# AFPGA_power.net
KiCad netlist of a schematic drawn in Altium Designer
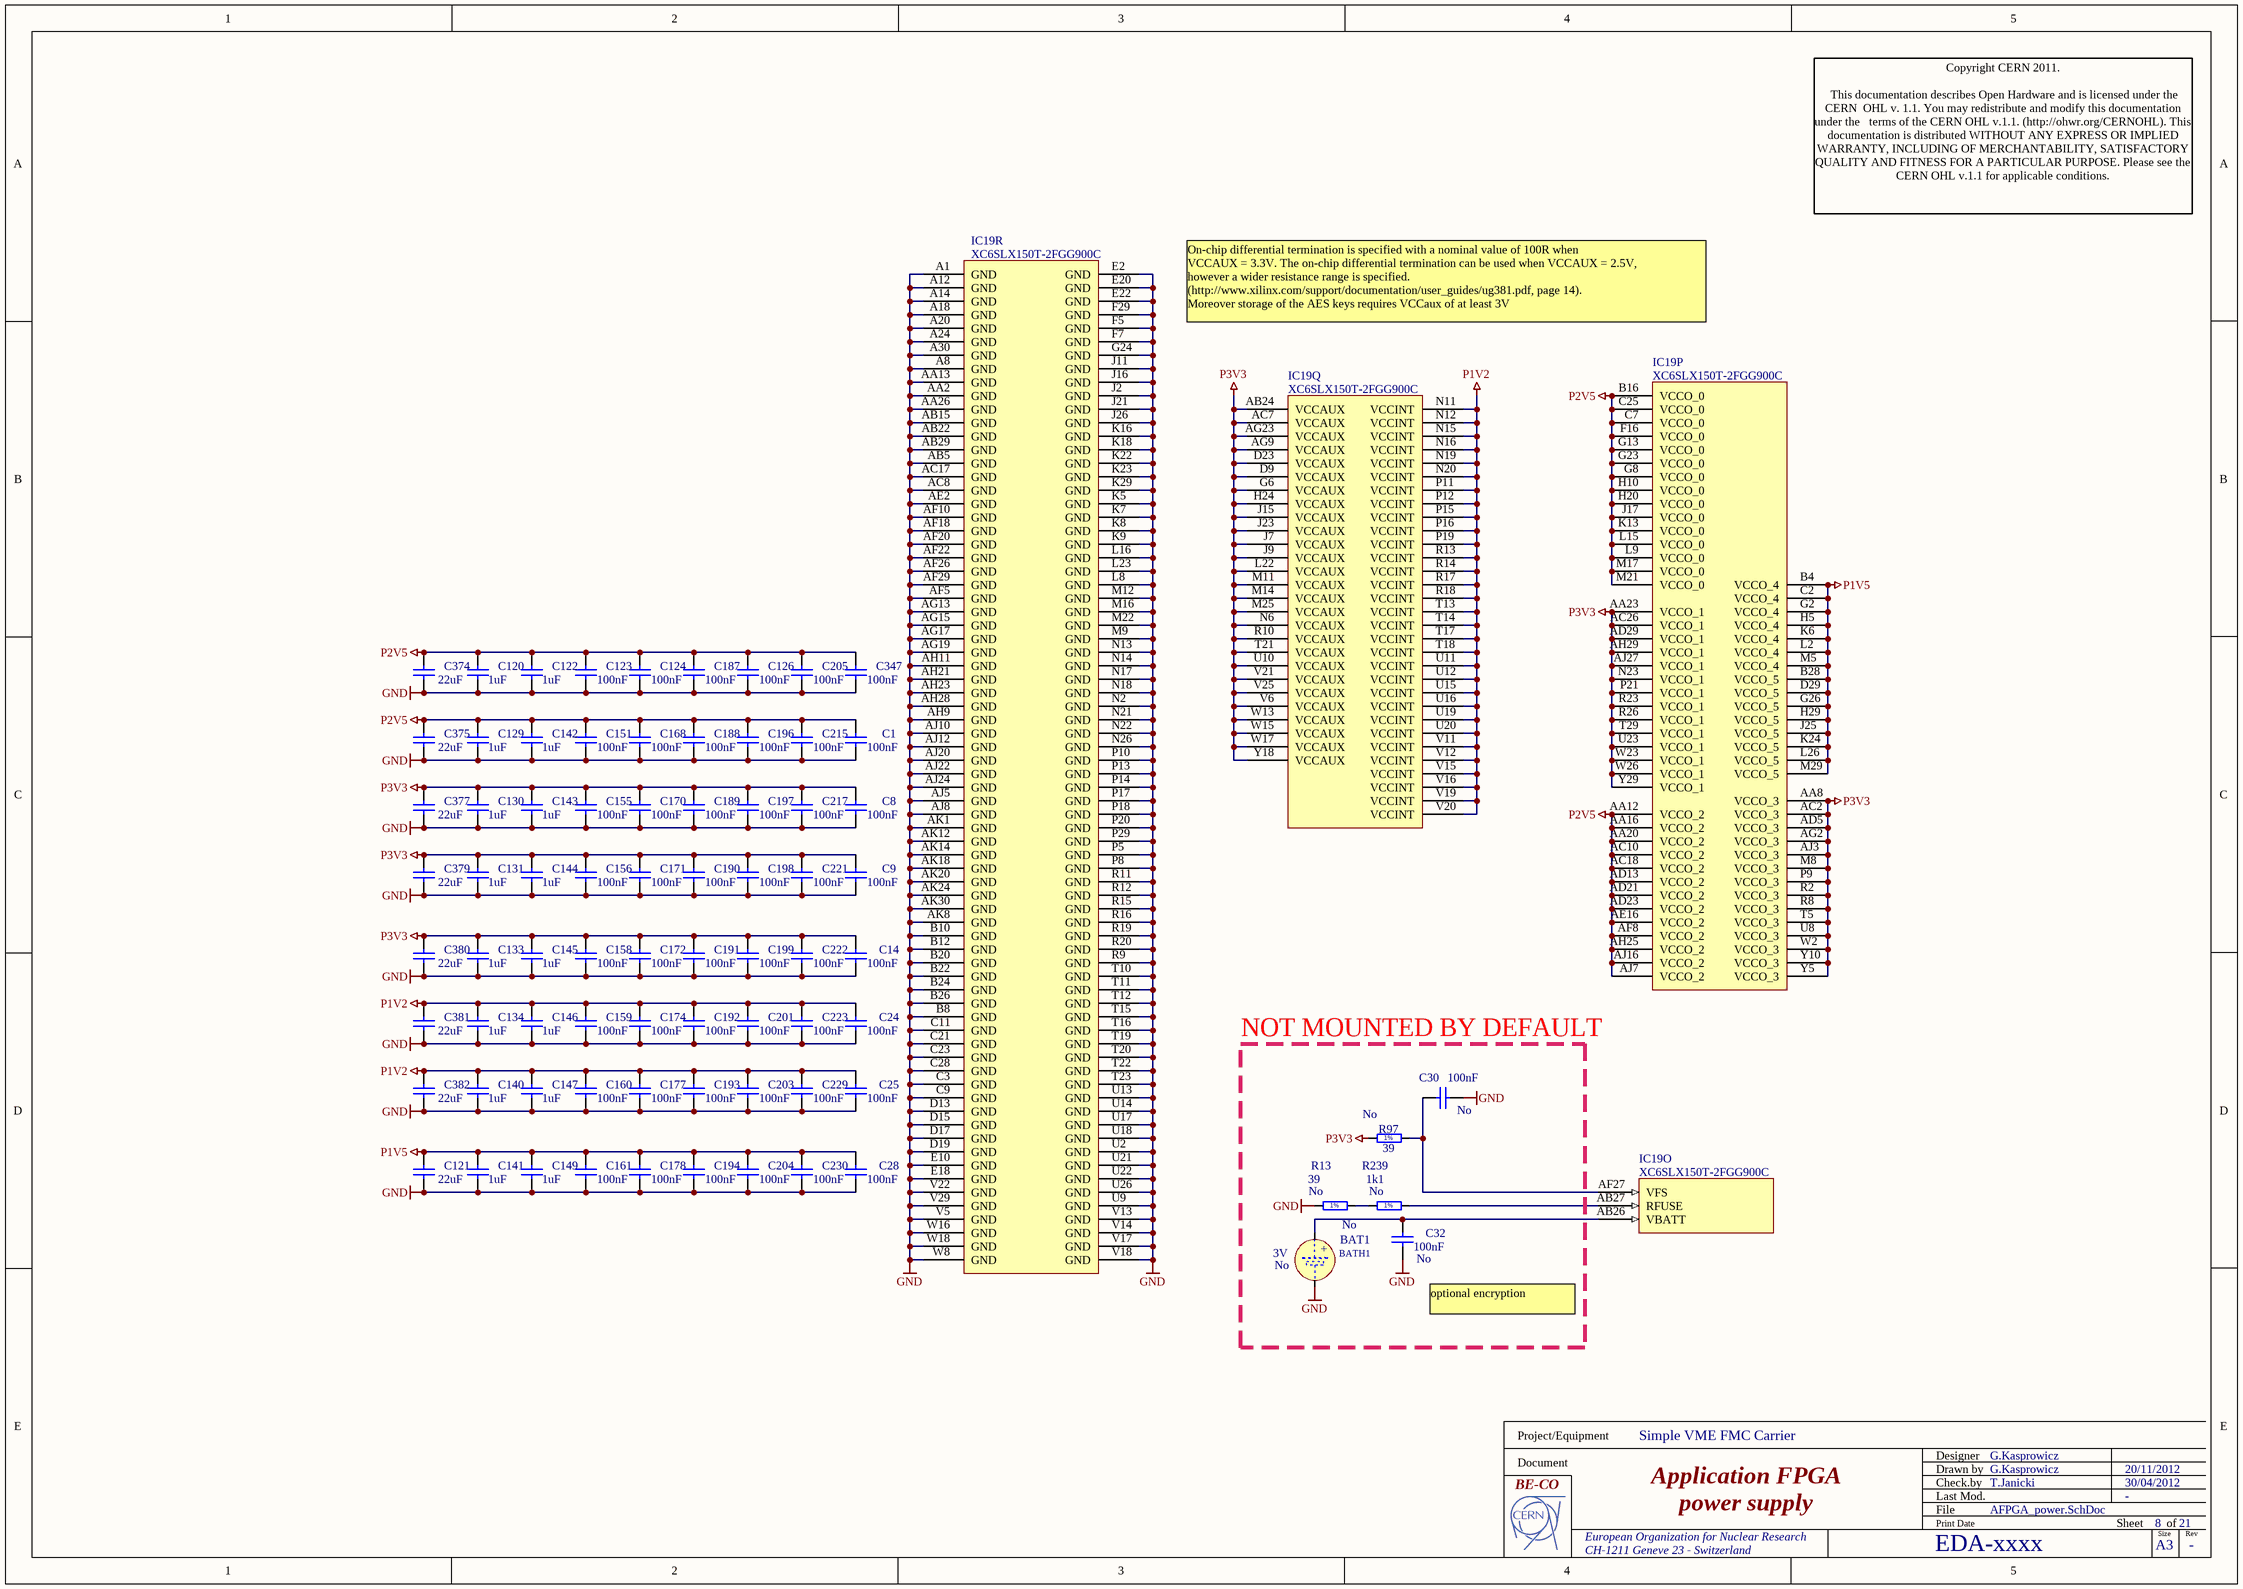
[diagram p0: AFPGA_power.SchDoc]

(export (version "E")
  (design (tool "Eeschema 10.0.6"))
  (components
    (comp (ref "BAT1")
      (value "3V")
      (footprint "BAT_VARTA_CR1220")
      (description "Battery for use only with Socket Holder")
      (fields
        (field (name "PART NUMBER") "BAT_VARTA_CR1220")
        (field (name "MOUNTED") "No")
        (field (name "POWER") "35mAh")
        (field (name "AUTHOR") "CERN DEM JLC")
      )
      (libsource (lib "Eletro-mechanical") (part "Battery No Pin"))
    )
    (comp (ref "BATH1")
      (value "~")
      (footprint "BATH_KEYSTONE_3000")
      (description "Battery Holder whit 2 Pin")
      (fields
        (field (name "PART NUMBER") "BATH_KEYSTONE_3000")
        (field (name "MOUNTED") "No")
        (field (name "MANUFACTURER") "KEYSTONE")
        (field (name "AUTHOR") "CERN DEM JLC")
      )
      (libsource (lib "Eletro-mechanical") (part "Battery Holder 2 Pin"))
    )
    (comp (ref "C1")
      (value "100nF")
      (footprint "CAPC1005X55N")
      (description "Non-polarised capacitor")
      (fields
        (field (name "PART NUMBER") "CC0402_100NF_16V_10%_X7R")
        (field (name "VOLTAGE") "16V")
        (field (name "AUTHOR") "CERN DEM JLC")
      )
      (libsource (lib "Capacitors") (part "Capacitor - non polarized"))
    )
    (comp (ref "C8")
      (value "100nF")
      (footprint "CAPC1005X55N")
      (description "Non-polarised capacitor")
      (fields
        (field (name "PART NUMBER") "CC0402_100NF_16V_10%_X7R")
        (field (name "VOLTAGE") "16V")
        (field (name "AUTHOR") "CERN DEM JLC")
      )
      (libsource (lib "Capacitors") (part "Capacitor - non polarized"))
    )
    (comp (ref "C9")
      (value "100nF")
      (footprint "CAPC1005X55N")
      (description "Non-polarised capacitor")
      (fields
        (field (name "PART NUMBER") "CC0402_100NF_16V_10%_X7R")
        (field (name "VOLTAGE") "16V")
        (field (name "AUTHOR") "CERN DEM JLC")
      )
      (libsource (lib "Capacitors") (part "Capacitor - non polarized"))
    )
    (comp (ref "C14")
      (value "100nF")
      (footprint "CAPC1005X55N")
      (description "Non-polarised capacitor")
      (fields
        (field (name "PART NUMBER") "CC0402_100NF_16V_10%_X7R")
        (field (name "VOLTAGE") "16V")
        (field (name "AUTHOR") "CERN DEM JLC")
      )
      (libsource (lib "Capacitors") (part "Capacitor - non polarized"))
    )
    (comp (ref "C24")
      (value "100nF")
      (footprint "CAPC1005X55N")
      (description "Non-polarised capacitor")
      (fields
        (field (name "PART NUMBER") "CC0402_100NF_16V_10%_X7R")
        (field (name "VOLTAGE") "16V")
        (field (name "AUTHOR") "CERN DEM JLC")
      )
      (libsource (lib "Capacitors") (part "Capacitor - non polarized"))
    )
    (comp (ref "C25")
      (value "100nF")
      (footprint "CAPC1005X55N")
      (description "Non-polarised capacitor")
      (fields
        (field (name "PART NUMBER") "CC0402_100NF_16V_10%_X7R")
        (field (name "VOLTAGE") "16V")
        (field (name "AUTHOR") "CERN DEM JLC")
      )
      (libsource (lib "Capacitors") (part "Capacitor - non polarized"))
    )
    (comp (ref "C28")
      (value "100nF")
      (footprint "CAPC1005X55N")
      (description "Non-polarised capacitor")
      (fields
        (field (name "PART NUMBER") "CC0402_100NF_16V_10%_X7R")
        (field (name "VOLTAGE") "16V")
        (field (name "AUTHOR") "CERN DEM JLC")
      )
      (libsource (lib "Capacitors") (part "Capacitor - non polarized"))
    )
    (comp (ref "C30")
      (value "100nF")
      (footprint "CAPC1005X55N")
      (description "Non-polarised capacitor")
      (fields
        (field (name "PART NUMBER") "CC0402_100NF_16V_10%_X7R")
        (field (name "VOLTAGE") "16V")
        (field (name "MOUNTED") "No")
        (field (name "AUTHOR") "CERN DEM JLC")
      )
      (libsource (lib "Capacitors") (part "Capacitor - non polarized"))
    )
    (comp (ref "C32")
      (value "100nF")
      (footprint "CAPC1005X55N")
      (description "Non-polarised capacitor")
      (fields
        (field (name "PART NUMBER") "CC0402_100NF_16V_10%_X7R")
        (field (name "VOLTAGE") "16V")
        (field (name "MOUNTED") "No")
        (field (name "AUTHOR") "CERN DEM JLC")
      )
      (libsource (lib "Capacitors") (part "Capacitor - non polarized"))
    )
    (comp (ref "C120")
      (value "1uF")
      (footprint "CAPC1608X87N")
      (description "Non-polarised capacitor")
      (fields
        (field (name "PART NUMBER") "CC0603_1UF_16V_10%_X7R")
        (field (name "VOLTAGE") "16V")
        (field (name "AUTHOR") "CERN DEM JLC")
      )
      (libsource (lib "Capacitors") (part "Capacitor - non polarized"))
    )
    (comp (ref "C121")
      (value "22uF")
      (footprint "CAPC3216X180N")
      (description "Non-polarised capacitor")
      (fields
        (field (name "PART NUMBER") "CC1206_22UF_10V_10%_X7R")
        (field (name "VOLTAGE") "10V")
        (field (name "AUTHOR") "CERN DEM JLC")
      )
      (libsource (lib "Capacitors") (part "Capacitor - non polarized"))
    )
    (comp (ref "C122")
      (value "1uF")
      (footprint "CAPC1608X87N")
      (description "Non-polarised capacitor")
      (fields
        (field (name "PART NUMBER") "CC0603_1UF_16V_10%_X7R")
        (field (name "VOLTAGE") "16V")
        (field (name "AUTHOR") "CERN DEM JLC")
      )
      (libsource (lib "Capacitors") (part "Capacitor - non polarized"))
    )
    (comp (ref "C123")
      (value "100nF")
      (footprint "CAPC1005X55N")
      (description "Non-polarised capacitor")
      (fields
        (field (name "PART NUMBER") "CC0402_100NF_16V_10%_X7R")
        (field (name "VOLTAGE") "16V")
        (field (name "AUTHOR") "CERN DEM JLC")
      )
      (libsource (lib "Capacitors") (part "Capacitor - non polarized"))
    )
    (comp (ref "C124")
      (value "100nF")
      (footprint "CAPC1005X55N")
      (description "Non-polarised capacitor")
      (fields
        (field (name "PART NUMBER") "CC0402_100NF_16V_10%_X7R")
        (field (name "VOLTAGE") "16V")
        (field (name "AUTHOR") "CERN DEM JLC")
      )
      (libsource (lib "Capacitors") (part "Capacitor - non polarized"))
    )
    (comp (ref "C126")
      (value "100nF")
      (footprint "CAPC1005X55N")
      (description "Non-polarised capacitor")
      (fields
        (field (name "PART NUMBER") "CC0402_100NF_16V_10%_X7R")
        (field (name "VOLTAGE") "16V")
        (field (name "AUTHOR") "CERN DEM JLC")
      )
      (libsource (lib "Capacitors") (part "Capacitor - non polarized"))
    )
    (comp (ref "C129")
      (value "1uF")
      (footprint "CAPC1608X87N")
      (description "Non-polarised capacitor")
      (fields
        (field (name "PART NUMBER") "CC0603_1UF_16V_10%_X7R")
        (field (name "VOLTAGE") "16V")
        (field (name "AUTHOR") "CERN DEM JLC")
      )
      (libsource (lib "Capacitors") (part "Capacitor - non polarized"))
    )
    (comp (ref "C130")
      (value "1uF")
      (footprint "CAPC1608X87N")
      (description "Non-polarised capacitor")
      (fields
        (field (name "PART NUMBER") "CC0603_1UF_16V_10%_X7R")
        (field (name "VOLTAGE") "16V")
        (field (name "AUTHOR") "CERN DEM JLC")
      )
      (libsource (lib "Capacitors") (part "Capacitor - non polarized"))
    )
    (comp (ref "C131")
      (value "1uF")
      (footprint "CAPC1608X87N")
      (description "Non-polarised capacitor")
      (fields
        (field (name "PART NUMBER") "CC0603_1UF_16V_10%_X7R")
        (field (name "VOLTAGE") "16V")
        (field (name "AUTHOR") "CERN DEM JLC")
      )
      (libsource (lib "Capacitors") (part "Capacitor - non polarized"))
    )
    (comp (ref "C133")
      (value "1uF")
      (footprint "CAPC1608X87N")
      (description "Non-polarised capacitor")
      (fields
        (field (name "PART NUMBER") "CC0603_1UF_16V_10%_X7R")
        (field (name "VOLTAGE") "16V")
        (field (name "AUTHOR") "CERN DEM JLC")
      )
      (libsource (lib "Capacitors") (part "Capacitor - non polarized"))
    )
    (comp (ref "C134")
      (value "1uF")
      (footprint "CAPC1608X87N")
      (description "Non-polarised capacitor")
      (fields
        (field (name "PART NUMBER") "CC0603_1UF_16V_10%_X7R")
        (field (name "VOLTAGE") "16V")
        (field (name "AUTHOR") "CERN DEM JLC")
      )
      (libsource (lib "Capacitors") (part "Capacitor - non polarized"))
    )
    (comp (ref "C140")
      (value "1uF")
      (footprint "CAPC1608X87N")
      (description "Non-polarised capacitor")
      (fields
        (field (name "PART NUMBER") "CC0603_1UF_16V_10%_X7R")
        (field (name "VOLTAGE") "16V")
        (field (name "AUTHOR") "CERN DEM JLC")
      )
      (libsource (lib "Capacitors") (part "Capacitor - non polarized"))
    )
    (comp (ref "C141")
      (value "1uF")
      (footprint "CAPC1608X87N")
      (description "Non-polarised capacitor")
      (fields
        (field (name "PART NUMBER") "CC0603_1UF_16V_10%_X7R")
        (field (name "VOLTAGE") "16V")
        (field (name "AUTHOR") "CERN DEM JLC")
      )
      (libsource (lib "Capacitors") (part "Capacitor - non polarized"))
    )
    (comp (ref "C142")
      (value "1uF")
      (footprint "CAPC1608X87N")
      (description "Non-polarised capacitor")
      (fields
        (field (name "PART NUMBER") "CC0603_1UF_16V_10%_X7R")
        (field (name "VOLTAGE") "16V")
        (field (name "AUTHOR") "CERN DEM JLC")
      )
      (libsource (lib "Capacitors") (part "Capacitor - non polarized"))
    )
    (comp (ref "C143")
      (value "1uF")
      (footprint "CAPC1608X87N")
      (description "Non-polarised capacitor")
      (fields
        (field (name "PART NUMBER") "CC0603_1UF_16V_10%_X7R")
        (field (name "VOLTAGE") "16V")
        (field (name "AUTHOR") "CERN DEM JLC")
      )
      (libsource (lib "Capacitors") (part "Capacitor - non polarized"))
    )
    (comp (ref "C144")
      (value "1uF")
      (footprint "CAPC1608X87N")
      (description "Non-polarised capacitor")
      (fields
        (field (name "PART NUMBER") "CC0603_1UF_16V_10%_X7R")
        (field (name "VOLTAGE") "16V")
        (field (name "AUTHOR") "CERN DEM JLC")
      )
      (libsource (lib "Capacitors") (part "Capacitor - non polarized"))
    )
    (comp (ref "C145")
      (value "1uF")
      (footprint "CAPC1608X87N")
      (description "Non-polarised capacitor")
      (fields
        (field (name "PART NUMBER") "CC0603_1UF_16V_10%_X7R")
        (field (name "VOLTAGE") "16V")
        (field (name "AUTHOR") "CERN DEM JLC")
      )
      (libsource (lib "Capacitors") (part "Capacitor - non polarized"))
    )
    (comp (ref "C146")
      (value "1uF")
      (footprint "CAPC1608X87N")
      (description "Non-polarised capacitor")
      (fields
        (field (name "PART NUMBER") "CC0603_1UF_16V_10%_X7R")
        (field (name "VOLTAGE") "16V")
        (field (name "AUTHOR") "CERN DEM JLC")
      )
      (libsource (lib "Capacitors") (part "Capacitor - non polarized"))
    )
    (comp (ref "C147")
      (value "1uF")
      (footprint "CAPC1608X87N")
      (description "Non-polarised capacitor")
      (fields
        (field (name "PART NUMBER") "CC0603_1UF_16V_10%_X7R")
        (field (name "VOLTAGE") "16V")
        (field (name "AUTHOR") "CERN DEM JLC")
      )
      (libsource (lib "Capacitors") (part "Capacitor - non polarized"))
    )
    (comp (ref "C149")
      (value "1uF")
      (footprint "CAPC1608X87N")
      (description "Non-polarised capacitor")
      (fields
        (field (name "PART NUMBER") "CC0603_1UF_16V_10%_X7R")
        (field (name "VOLTAGE") "16V")
        (field (name "AUTHOR") "CERN DEM JLC")
      )
      (libsource (lib "Capacitors") (part "Capacitor - non polarized"))
    )
    (comp (ref "C151")
      (value "100nF")
      (footprint "CAPC1005X55N")
      (description "Non-polarised capacitor")
      (fields
        (field (name "PART NUMBER") "CC0402_100NF_16V_10%_X7R")
        (field (name "VOLTAGE") "16V")
        (field (name "AUTHOR") "CERN DEM JLC")
      )
      (libsource (lib "Capacitors") (part "Capacitor - non polarized"))
    )
    (comp (ref "C155")
      (value "100nF")
      (footprint "CAPC1005X55N")
      (description "Non-polarised capacitor")
      (fields
        (field (name "PART NUMBER") "CC0402_100NF_16V_10%_X7R")
        (field (name "VOLTAGE") "16V")
        (field (name "AUTHOR") "CERN DEM JLC")
      )
      (libsource (lib "Capacitors") (part "Capacitor - non polarized"))
    )
    (comp (ref "C156")
      (value "100nF")
      (footprint "CAPC1005X55N")
      (description "Non-polarised capacitor")
      (fields
        (field (name "PART NUMBER") "CC0402_100NF_16V_10%_X7R")
        (field (name "VOLTAGE") "16V")
        (field (name "AUTHOR") "CERN DEM JLC")
      )
      (libsource (lib "Capacitors") (part "Capacitor - non polarized"))
    )
    (comp (ref "C158")
      (value "100nF")
      (footprint "CAPC1005X55N")
      (description "Non-polarised capacitor")
      (fields
        (field (name "PART NUMBER") "CC0402_100NF_16V_10%_X7R")
        (field (name "VOLTAGE") "16V")
        (field (name "AUTHOR") "CERN DEM JLC")
      )
      (libsource (lib "Capacitors") (part "Capacitor - non polarized"))
    )
    (comp (ref "C159")
      (value "100nF")
      (footprint "CAPC1005X55N")
      (description "Non-polarised capacitor")
      (fields
        (field (name "PART NUMBER") "CC0402_100NF_16V_10%_X7R")
        (field (name "VOLTAGE") "16V")
        (field (name "AUTHOR") "CERN DEM JLC")
      )
      (libsource (lib "Capacitors") (part "Capacitor - non polarized"))
    )
    (comp (ref "C160")
      (value "100nF")
      (footprint "CAPC1005X55N")
      (description "Non-polarised capacitor")
      (fields
        (field (name "PART NUMBER") "CC0402_100NF_16V_10%_X7R")
        (field (name "VOLTAGE") "16V")
        (field (name "AUTHOR") "CERN DEM JLC")
      )
      (libsource (lib "Capacitors") (part "Capacitor - non polarized"))
    )
    (comp (ref "C161")
      (value "100nF")
      (footprint "CAPC1005X55N")
      (description "Non-polarised capacitor")
      (fields
        (field (name "PART NUMBER") "CC0402_100NF_16V_10%_X7R")
        (field (name "VOLTAGE") "16V")
        (field (name "AUTHOR") "CERN DEM JLC")
      )
      (libsource (lib "Capacitors") (part "Capacitor - non polarized"))
    )
    (comp (ref "C168")
      (value "100nF")
      (footprint "CAPC1005X55N")
      (description "Non-polarised capacitor")
      (fields
        (field (name "PART NUMBER") "CC0402_100NF_16V_10%_X7R")
        (field (name "VOLTAGE") "16V")
        (field (name "AUTHOR") "CERN DEM JLC")
      )
      (libsource (lib "Capacitors") (part "Capacitor - non polarized"))
    )
    (comp (ref "C170")
      (value "100nF")
      (footprint "CAPC1005X55N")
      (description "Non-polarised capacitor")
      (fields
        (field (name "PART NUMBER") "CC0402_100NF_16V_10%_X7R")
        (field (name "VOLTAGE") "16V")
        (field (name "AUTHOR") "CERN DEM JLC")
      )
      (libsource (lib "Capacitors") (part "Capacitor - non polarized"))
    )
    (comp (ref "C171")
      (value "100nF")
      (footprint "CAPC1005X55N")
      (description "Non-polarised capacitor")
      (fields
        (field (name "PART NUMBER") "CC0402_100NF_16V_10%_X7R")
        (field (name "VOLTAGE") "16V")
        (field (name "AUTHOR") "CERN DEM JLC")
      )
      (libsource (lib "Capacitors") (part "Capacitor - non polarized"))
    )
    (comp (ref "C172")
      (value "100nF")
      (footprint "CAPC1005X55N")
      (description "Non-polarised capacitor")
      (fields
        (field (name "PART NUMBER") "CC0402_100NF_16V_10%_X7R")
        (field (name "VOLTAGE") "16V")
        (field (name "AUTHOR") "CERN DEM JLC")
      )
      (libsource (lib "Capacitors") (part "Capacitor - non polarized"))
    )
    (comp (ref "C174")
      (value "100nF")
      (footprint "CAPC1005X55N")
      (description "Non-polarised capacitor")
      (fields
        (field (name "PART NUMBER") "CC0402_100NF_16V_10%_X7R")
        (field (name "VOLTAGE") "16V")
        (field (name "AUTHOR") "CERN DEM JLC")
      )
      (libsource (lib "Capacitors") (part "Capacitor - non polarized"))
    )
    (comp (ref "C177")
      (value "100nF")
      (footprint "CAPC1005X55N")
      (description "Non-polarised capacitor")
      (fields
        (field (name "PART NUMBER") "CC0402_100NF_16V_10%_X7R")
        (field (name "VOLTAGE") "16V")
        (field (name "AUTHOR") "CERN DEM JLC")
      )
      (libsource (lib "Capacitors") (part "Capacitor - non polarized"))
    )
    (comp (ref "C178")
      (value "100nF")
      (footprint "CAPC1005X55N")
      (description "Non-polarised capacitor")
      (fields
        (field (name "PART NUMBER") "CC0402_100NF_16V_10%_X7R")
        (field (name "VOLTAGE") "16V")
        (field (name "AUTHOR") "CERN DEM JLC")
      )
      (libsource (lib "Capacitors") (part "Capacitor - non polarized"))
    )
    (comp (ref "C187")
      (value "100nF")
      (footprint "CAPC1005X55N")
      (description "Non-polarised capacitor")
      (fields
        (field (name "PART NUMBER") "CC0402_100NF_16V_10%_X7R")
        (field (name "VOLTAGE") "16V")
        (field (name "AUTHOR") "CERN DEM JLC")
      )
      (libsource (lib "Capacitors") (part "Capacitor - non polarized"))
    )
    (comp (ref "C188")
      (value "100nF")
      (footprint "CAPC1005X55N")
      (description "Non-polarised capacitor")
      (fields
        (field (name "PART NUMBER") "CC0402_100NF_16V_10%_X7R")
        (field (name "VOLTAGE") "16V")
        (field (name "AUTHOR") "CERN DEM JLC")
      )
      (libsource (lib "Capacitors") (part "Capacitor - non polarized"))
    )
    (comp (ref "C189")
      (value "100nF")
      (footprint "CAPC1005X55N")
      (description "Non-polarised capacitor")
      (fields
        (field (name "PART NUMBER") "CC0402_100NF_16V_10%_X7R")
        (field (name "VOLTAGE") "16V")
        (field (name "AUTHOR") "CERN DEM JLC")
      )
      (libsource (lib "Capacitors") (part "Capacitor - non polarized"))
    )
    (comp (ref "C190")
      (value "100nF")
      (footprint "CAPC1005X55N")
      (description "Non-polarised capacitor")
      (fields
        (field (name "PART NUMBER") "CC0402_100NF_16V_10%_X7R")
        (field (name "VOLTAGE") "16V")
        (field (name "AUTHOR") "CERN DEM JLC")
      )
      (libsource (lib "Capacitors") (part "Capacitor - non polarized"))
    )
    (comp (ref "C191")
      (value "100nF")
      (footprint "CAPC1005X55N")
      (description "Non-polarised capacitor")
      (fields
        (field (name "PART NUMBER") "CC0402_100NF_16V_10%_X7R")
        (field (name "VOLTAGE") "16V")
        (field (name "AUTHOR") "CERN DEM JLC")
      )
      (libsource (lib "Capacitors") (part "Capacitor - non polarized"))
    )
    (comp (ref "C192")
      (value "100nF")
      (footprint "CAPC1005X55N")
      (description "Non-polarised capacitor")
      (fields
        (field (name "PART NUMBER") "CC0402_100NF_16V_10%_X7R")
        (field (name "VOLTAGE") "16V")
        (field (name "AUTHOR") "CERN DEM JLC")
      )
      (libsource (lib "Capacitors") (part "Capacitor - non polarized"))
    )
    (comp (ref "C193")
      (value "100nF")
      (footprint "CAPC1005X55N")
      (description "Non-polarised capacitor")
      (fields
        (field (name "PART NUMBER") "CC0402_100NF_16V_10%_X7R")
        (field (name "VOLTAGE") "16V")
        (field (name "AUTHOR") "CERN DEM JLC")
      )
      (libsource (lib "Capacitors") (part "Capacitor - non polarized"))
    )
    (comp (ref "C194")
      (value "100nF")
      (footprint "CAPC1005X55N")
      (description "Non-polarised capacitor")
      (fields
        (field (name "PART NUMBER") "CC0402_100NF_16V_10%_X7R")
        (field (name "VOLTAGE") "16V")
        (field (name "AUTHOR") "CERN DEM JLC")
      )
      (libsource (lib "Capacitors") (part "Capacitor - non polarized"))
    )
    (comp (ref "C196")
      (value "100nF")
      (footprint "CAPC1005X55N")
      (description "Non-polarised capacitor")
      (fields
        (field (name "PART NUMBER") "CC0402_100NF_16V_10%_X7R")
        (field (name "VOLTAGE") "16V")
        (field (name "AUTHOR") "CERN DEM JLC")
      )
      (libsource (lib "Capacitors") (part "Capacitor - non polarized"))
    )
    (comp (ref "C197")
      (value "100nF")
      (footprint "CAPC1005X55N")
      (description "Non-polarised capacitor")
      (fields
        (field (name "PART NUMBER") "CC0402_100NF_16V_10%_X7R")
        (field (name "VOLTAGE") "16V")
        (field (name "AUTHOR") "CERN DEM JLC")
      )
      (libsource (lib "Capacitors") (part "Capacitor - non polarized"))
    )
    (comp (ref "C198")
      (value "100nF")
      (footprint "CAPC1005X55N")
      (description "Non-polarised capacitor")
      (fields
        (field (name "PART NUMBER") "CC0402_100NF_16V_10%_X7R")
        (field (name "VOLTAGE") "16V")
        (field (name "AUTHOR") "CERN DEM JLC")
      )
      (libsource (lib "Capacitors") (part "Capacitor - non polarized"))
    )
    (comp (ref "C199")
      (value "100nF")
      (footprint "CAPC1005X55N")
      (description "Non-polarised capacitor")
      (fields
        (field (name "PART NUMBER") "CC0402_100NF_16V_10%_X7R")
        (field (name "VOLTAGE") "16V")
        (field (name "AUTHOR") "CERN DEM JLC")
      )
      (libsource (lib "Capacitors") (part "Capacitor - non polarized"))
    )
    (comp (ref "C201")
      (value "100nF")
      (footprint "CAPC1005X55N")
      (description "Non-polarised capacitor")
      (fields
        (field (name "PART NUMBER") "CC0402_100NF_16V_10%_X7R")
        (field (name "VOLTAGE") "16V")
        (field (name "AUTHOR") "CERN DEM JLC")
      )
      (libsource (lib "Capacitors") (part "Capacitor - non polarized"))
    )
    (comp (ref "C203")
      (value "100nF")
      (footprint "CAPC1005X55N")
      (description "Non-polarised capacitor")
      (fields
        (field (name "PART NUMBER") "CC0402_100NF_16V_10%_X7R")
        (field (name "VOLTAGE") "16V")
        (field (name "AUTHOR") "CERN DEM JLC")
      )
      (libsource (lib "Capacitors") (part "Capacitor - non polarized"))
    )
    (comp (ref "C204")
      (value "100nF")
      (footprint "CAPC1005X55N")
      (description "Non-polarised capacitor")
      (fields
        (field (name "PART NUMBER") "CC0402_100NF_16V_10%_X7R")
        (field (name "VOLTAGE") "16V")
        (field (name "AUTHOR") "CERN DEM JLC")
      )
      (libsource (lib "Capacitors") (part "Capacitor - non polarized"))
    )
    (comp (ref "C205")
      (value "100nF")
      (footprint "CAPC1005X55N")
      (description "Non-polarised capacitor")
      (fields
        (field (name "PART NUMBER") "CC0402_100NF_16V_10%_X7R")
        (field (name "VOLTAGE") "16V")
        (field (name "AUTHOR") "CERN DEM JLC")
      )
      (libsource (lib "Capacitors") (part "Capacitor - non polarized"))
    )
    (comp (ref "C215")
      (value "100nF")
      (footprint "CAPC1005X55N")
      (description "Non-polarised capacitor")
      (fields
        (field (name "PART NUMBER") "CC0402_100NF_16V_10%_X7R")
        (field (name "VOLTAGE") "16V")
        (field (name "AUTHOR") "CERN DEM JLC")
      )
      (libsource (lib "Capacitors") (part "Capacitor - non polarized"))
    )
    (comp (ref "C217")
      (value "100nF")
      (footprint "CAPC1005X55N")
      (description "Non-polarised capacitor")
      (fields
        (field (name "PART NUMBER") "CC0402_100NF_16V_10%_X7R")
        (field (name "VOLTAGE") "16V")
        (field (name "AUTHOR") "CERN DEM JLC")
      )
      (libsource (lib "Capacitors") (part "Capacitor - non polarized"))
    )
    (comp (ref "C221")
      (value "100nF")
      (footprint "CAPC1005X55N")
      (description "Non-polarised capacitor")
      (fields
        (field (name "PART NUMBER") "CC0402_100NF_16V_10%_X7R")
        (field (name "VOLTAGE") "16V")
        (field (name "AUTHOR") "CERN DEM JLC")
      )
      (libsource (lib "Capacitors") (part "Capacitor - non polarized"))
    )
    (comp (ref "C222")
      (value "100nF")
      (footprint "CAPC1005X55N")
      (description "Non-polarised capacitor")
      (fields
        (field (name "PART NUMBER") "CC0402_100NF_16V_10%_X7R")
        (field (name "VOLTAGE") "16V")
        (field (name "AUTHOR") "CERN DEM JLC")
      )
      (libsource (lib "Capacitors") (part "Capacitor - non polarized"))
    )
    (comp (ref "C223")
      (value "100nF")
      (footprint "CAPC1005X55N")
      (description "Non-polarised capacitor")
      (fields
        (field (name "PART NUMBER") "CC0402_100NF_16V_10%_X7R")
        (field (name "VOLTAGE") "16V")
        (field (name "AUTHOR") "CERN DEM JLC")
      )
      (libsource (lib "Capacitors") (part "Capacitor - non polarized"))
    )
    (comp (ref "C229")
      (value "100nF")
      (footprint "CAPC1005X55N")
      (description "Non-polarised capacitor")
      (fields
        (field (name "PART NUMBER") "CC0402_100NF_16V_10%_X7R")
        (field (name "VOLTAGE") "16V")
        (field (name "AUTHOR") "CERN DEM JLC")
      )
      (libsource (lib "Capacitors") (part "Capacitor - non polarized"))
    )
    (comp (ref "C230")
      (value "100nF")
      (footprint "CAPC1005X55N")
      (description "Non-polarised capacitor")
      (fields
        (field (name "PART NUMBER") "CC0402_100NF_16V_10%_X7R")
        (field (name "VOLTAGE") "16V")
        (field (name "AUTHOR") "CERN DEM JLC")
      )
      (libsource (lib "Capacitors") (part "Capacitor - non polarized"))
    )
    (comp (ref "C347")
      (value "100nF")
      (footprint "CAPC1005X55N")
      (description "Non-polarised capacitor")
      (fields
        (field (name "PART NUMBER") "CC0402_100NF_16V_10%_X7R")
        (field (name "VOLTAGE") "16V")
        (field (name "AUTHOR") "CERN DEM JLC")
      )
      (libsource (lib "Capacitors") (part "Capacitor - non polarized"))
    )
    (comp (ref "C374")
      (value "22uF")
      (footprint "CAPC3216X180N")
      (description "Non-polarised capacitor")
      (fields
        (field (name "PART NUMBER") "CC1206_22UF_10V_10%_X7R")
        (field (name "VOLTAGE") "10V")
        (field (name "AUTHOR") "CERN DEM JLC")
      )
      (libsource (lib "Capacitors") (part "Capacitor - non polarized"))
    )
    (comp (ref "C375")
      (value "22uF")
      (footprint "CAPC3216X180N")
      (description "Non-polarised capacitor")
      (fields
        (field (name "PART NUMBER") "CC1206_22UF_10V_10%_X7R")
        (field (name "VOLTAGE") "10V")
        (field (name "AUTHOR") "CERN DEM JLC")
      )
      (libsource (lib "Capacitors") (part "Capacitor - non polarized"))
    )
    (comp (ref "C377")
      (value "22uF")
      (footprint "CAPC3216X180N")
      (description "Non-polarised capacitor")
      (fields
        (field (name "PART NUMBER") "CC1206_22UF_10V_10%_X7R")
        (field (name "VOLTAGE") "10V")
        (field (name "AUTHOR") "CERN DEM JLC")
      )
      (libsource (lib "Capacitors") (part "Capacitor - non polarized"))
    )
    (comp (ref "C379")
      (value "22uF")
      (footprint "CAPC3216X180N")
      (description "Non-polarised capacitor")
      (fields
        (field (name "PART NUMBER") "CC1206_22UF_10V_10%_X7R")
        (field (name "VOLTAGE") "10V")
        (field (name "AUTHOR") "CERN DEM JLC")
      )
      (libsource (lib "Capacitors") (part "Capacitor - non polarized"))
    )
    (comp (ref "C380")
      (value "22uF")
      (footprint "CAPC3216X180N")
      (description "Non-polarised capacitor")
      (fields
        (field (name "PART NUMBER") "CC1206_22UF_10V_10%_X7R")
        (field (name "VOLTAGE") "10V")
        (field (name "AUTHOR") "CERN DEM JLC")
      )
      (libsource (lib "Capacitors") (part "Capacitor - non polarized"))
    )
    (comp (ref "C381")
      (value "22uF")
      (footprint "CAPC3216X180N")
      (description "Non-polarised capacitor")
      (fields
        (field (name "PART NUMBER") "CC1206_22UF_10V_10%_X7R")
        (field (name "VOLTAGE") "10V")
        (field (name "AUTHOR") "CERN DEM JLC")
      )
      (libsource (lib "Capacitors") (part "Capacitor - non polarized"))
    )
    (comp (ref "C382")
      (value "22uF")
      (footprint "CAPC3216X180N")
      (description "Non-polarised capacitor")
      (fields
        (field (name "PART NUMBER") "CC1206_22UF_10V_10%_X7R")
        (field (name "VOLTAGE") "10V")
        (field (name "AUTHOR") "CERN DEM JLC")
      )
      (libsource (lib "Capacitors") (part "Capacitor - non polarized"))
    )
    (comp (ref "IC19")
      (value "XC6SLX150T-2FGG900C")
      (footprint "BGA900C100P30X30_3100X3100X260")
      (description "SPARTAN-6, FPGA, 900-Ball BGA, Commercial Grade, Pb-Free")
      (fields (field (name "MANUFACTURER") "XILINX") (field (name "AUTHOR") "CERN DEM JLC"))
      (libsource (lib "ICs And Semiconductors") (part "XC6SLX150T-2FGG900C"))
    )
    (comp (ref "R13")
      (value "39")
      (footprint "RESC1608X55N")
      (description "Resistor - 1%")
      (fields
        (field (name "PART NUMBER") "R0603_39R_1%_0.1W_100PPM")
        (field (name "POWER") "0.1W")
        (field (name "MOUNTED") "No")
        (field (name "AUTHOR") "CERN DEM JLC")
      )
      (libsource (lib "Resistors") (part "Resistor - 1%"))
    )
    (comp (ref "R97")
      (value "39")
      (footprint "RESC1608X55N")
      (description "Resistor - 1%")
      (fields
        (field (name "PART NUMBER") "R0603_39R_1%_0.1W_100PPM")
        (field (name "POWER") "0.1W")
        (field (name "MOUNTED") "No")
        (field (name "AUTHOR") "CERN DEM JLC")
      )
      (libsource (lib "Resistors") (part "Resistor - 1%"))
    )
    (comp (ref "R239")
      (value "1k1")
      (footprint "RESC1608X55N")
      (description "Resistor - 1%")
      (fields
        (field (name "PART NUMBER") "R0603_1K1_1%_0.1W_100PPM")
        (field (name "POWER") "0.1W")
        (field (name "MOUNTED") "No")
        (field (name "AUTHOR") "CERN DEM JLC")
      )
      (libsource (lib "Resistors") (part "Resistor - 1%"))
    )
  )
  (nets
    (net (code "1") (name "GND") (class "Default")
      (node (ref "BATH1") (pin "2") (pinfunction "MINUS_2") (pintype "passive"))
      (node (ref "C1") (pin "1") (pinfunction "1_1") (pintype "passive"))
      (node (ref "C120") (pin "1") (pinfunction "1_1") (pintype "passive"))
      (node (ref "C121") (pin "1") (pinfunction "1_1") (pintype "passive"))
      (node (ref "C122") (pin "1") (pinfunction "1_1") (pintype "passive"))
      (node (ref "C123") (pin "1") (pinfunction "1_1") (pintype "passive"))
      (node (ref "C124") (pin "1") (pinfunction "1_1") (pintype "passive"))
      (node (ref "C126") (pin "1") (pinfunction "1_1") (pintype "passive"))
      (node (ref "C129") (pin "1") (pinfunction "1_1") (pintype "passive"))
      (node (ref "C130") (pin "1") (pinfunction "1_1") (pintype "passive"))
      (node (ref "C131") (pin "1") (pinfunction "1_1") (pintype "passive"))
      (node (ref "C133") (pin "1") (pinfunction "1_1") (pintype "passive"))
      (node (ref "C134") (pin "1") (pinfunction "1_1") (pintype "passive"))
      (node (ref "C14") (pin "1") (pinfunction "1_1") (pintype "passive"))
      (node (ref "C140") (pin "1") (pinfunction "1_1") (pintype "passive"))
      (node (ref "C141") (pin "1") (pinfunction "1_1") (pintype "passive"))
      (node (ref "C142") (pin "1") (pinfunction "1_1") (pintype "passive"))
      (node (ref "C143") (pin "1") (pinfunction "1_1") (pintype "passive"))
      (node (ref "C144") (pin "1") (pinfunction "1_1") (pintype "passive"))
      (node (ref "C145") (pin "1") (pinfunction "1_1") (pintype "passive"))
      (node (ref "C146") (pin "1") (pinfunction "1_1") (pintype "passive"))
      (node (ref "C147") (pin "1") (pinfunction "1_1") (pintype "passive"))
      (node (ref "C149") (pin "1") (pinfunction "1_1") (pintype "passive"))
      (node (ref "C151") (pin "1") (pinfunction "1_1") (pintype "passive"))
      (node (ref "C155") (pin "1") (pinfunction "1_1") (pintype "passive"))
      (node (ref "C156") (pin "1") (pinfunction "1_1") (pintype "passive"))
      (node (ref "C158") (pin "1") (pinfunction "1_1") (pintype "passive"))
      (node (ref "C159") (pin "1") (pinfunction "1_1") (pintype "passive"))
      (node (ref "C160") (pin "1") (pinfunction "1_1") (pintype "passive"))
      (node (ref "C161") (pin "1") (pinfunction "1_1") (pintype "passive"))
      (node (ref "C168") (pin "1") (pinfunction "1_1") (pintype "passive"))
      (node (ref "C170") (pin "1") (pinfunction "1_1") (pintype "passive"))
      (node (ref "C171") (pin "1") (pinfunction "1_1") (pintype "passive"))
      (node (ref "C172") (pin "1") (pinfunction "1_1") (pintype "passive"))
      (node (ref "C174") (pin "1") (pinfunction "1_1") (pintype "passive"))
      (node (ref "C177") (pin "1") (pinfunction "1_1") (pintype "passive"))
      (node (ref "C178") (pin "1") (pinfunction "1_1") (pintype "passive"))
      (node (ref "C187") (pin "1") (pinfunction "1_1") (pintype "passive"))
      (node (ref "C188") (pin "1") (pinfunction "1_1") (pintype "passive"))
      (node (ref "C189") (pin "1") (pinfunction "1_1") (pintype "passive"))
      (node (ref "C190") (pin "1") (pinfunction "1_1") (pintype "passive"))
      (node (ref "C191") (pin "1") (pinfunction "1_1") (pintype "passive"))
      (node (ref "C192") (pin "1") (pinfunction "1_1") (pintype "passive"))
      (node (ref "C193") (pin "1") (pinfunction "1_1") (pintype "passive"))
      (node (ref "C194") (pin "1") (pinfunction "1_1") (pintype "passive"))
      (node (ref "C196") (pin "1") (pinfunction "1_1") (pintype "passive"))
      (node (ref "C197") (pin "1") (pinfunction "1_1") (pintype "passive"))
      (node (ref "C198") (pin "1") (pinfunction "1_1") (pintype "passive"))
      (node (ref "C199") (pin "1") (pinfunction "1_1") (pintype "passive"))
      (node (ref "C201") (pin "1") (pinfunction "1_1") (pintype "passive"))
      (node (ref "C203") (pin "1") (pinfunction "1_1") (pintype "passive"))
      (node (ref "C204") (pin "1") (pinfunction "1_1") (pintype "passive"))
      (node (ref "C205") (pin "1") (pinfunction "1_1") (pintype "passive"))
      (node (ref "C215") (pin "1") (pinfunction "1_1") (pintype "passive"))
      (node (ref "C217") (pin "1") (pinfunction "1_1") (pintype "passive"))
      (node (ref "C221") (pin "1") (pinfunction "1_1") (pintype "passive"))
      (node (ref "C222") (pin "1") (pinfunction "1_1") (pintype "passive"))
      (node (ref "C223") (pin "1") (pinfunction "1_1") (pintype "passive"))
      (node (ref "C229") (pin "1") (pinfunction "1_1") (pintype "passive"))
      (node (ref "C230") (pin "1") (pinfunction "1_1") (pintype "passive"))
      (node (ref "C24") (pin "1") (pinfunction "1_1") (pintype "passive"))
      (node (ref "C25") (pin "1") (pinfunction "1_1") (pintype "passive"))
      (node (ref "C28") (pin "1") (pinfunction "1_1") (pintype "passive"))
      (node (ref "C30") (pin "1") (pinfunction "1_1") (pintype "passive"))
      (node (ref "C32") (pin "1") (pinfunction "1_1") (pintype "passive"))
      (node (ref "C347") (pin "1") (pinfunction "1_1") (pintype "passive"))
      (node (ref "C374") (pin "1") (pinfunction "1_1") (pintype "passive"))
      (node (ref "C375") (pin "1") (pinfunction "1_1") (pintype "passive"))
      (node (ref "C377") (pin "1") (pinfunction "1_1") (pintype "passive"))
      (node (ref "C379") (pin "1") (pinfunction "1_1") (pintype "passive"))
      (node (ref "C380") (pin "1") (pinfunction "1_1") (pintype "passive"))
      (node (ref "C381") (pin "1") (pinfunction "1_1") (pintype "passive"))
      (node (ref "C382") (pin "1") (pinfunction "1_1") (pintype "passive"))
      (node (ref "C8") (pin "1") (pinfunction "1_1") (pintype "passive"))
      (node (ref "C9") (pin "1") (pinfunction "1_1") (pintype "passive"))
      (node (ref "IC19") (pin "A1") (pinfunction "GND_A1") (pintype "power_in"))
      (node (ref "IC19") (pin "A12") (pinfunction "GND_A12") (pintype "power_in"))
      (node (ref "IC19") (pin "A14") (pinfunction "GND_A14") (pintype "power_in"))
      (node (ref "IC19") (pin "A18") (pinfunction "GND_A18") (pintype "power_in"))
      (node (ref "IC19") (pin "A20") (pinfunction "GND_A20") (pintype "power_in"))
      (node (ref "IC19") (pin "A24") (pinfunction "GND_A24") (pintype "power_in"))
      (node (ref "IC19") (pin "A30") (pinfunction "GND_A30") (pintype "power_in"))
      (node (ref "IC19") (pin "A8") (pinfunction "GND_A8") (pintype "power_in"))
      (node (ref "IC19") (pin "AA13") (pinfunction "GND_AA13") (pintype "power_in"))
      (node (ref "IC19") (pin "AA2") (pinfunction "GND_AA2") (pintype "power_in"))
      (node (ref "IC19") (pin "AA26") (pinfunction "GND_AA26") (pintype "power_in"))
      (node (ref "IC19") (pin "AB15") (pinfunction "GND_AB15") (pintype "power_in"))
      (node (ref "IC19") (pin "AB22") (pinfunction "GND_AB22") (pintype "power_in"))
      (node (ref "IC19") (pin "AB29") (pinfunction "GND_AB29") (pintype "power_in"))
      (node (ref "IC19") (pin "AB5") (pinfunction "GND_AB5") (pintype "power_in"))
      (node (ref "IC19") (pin "AC17") (pinfunction "GND_AC17") (pintype "power_in"))
      (node (ref "IC19") (pin "AC8") (pinfunction "GND_AC8") (pintype "power_in"))
      (node (ref "IC19") (pin "AE2") (pinfunction "GND_AE2") (pintype "power_in"))
      (node (ref "IC19") (pin "AF10") (pinfunction "GND_AF10") (pintype "power_in"))
      (node (ref "IC19") (pin "AF18") (pinfunction "GND_AF18") (pintype "power_in"))
      (node (ref "IC19") (pin "AF20") (pinfunction "GND_AF20") (pintype "power_in"))
      (node (ref "IC19") (pin "AF22") (pinfunction "GND_AF22") (pintype "power_in"))
      (node (ref "IC19") (pin "AF26") (pinfunction "GND_AF26") (pintype "power_in"))
      (node (ref "IC19") (pin "AF29") (pinfunction "GND_AF29") (pintype "power_in"))
      (node (ref "IC19") (pin "AF5") (pinfunction "GND_AF5") (pintype "power_in"))
      (node (ref "IC19") (pin "AG13") (pinfunction "GND_AG13") (pintype "power_in"))
      (node (ref "IC19") (pin "AG15") (pinfunction "GND_AG15") (pintype "power_in"))
      (node (ref "IC19") (pin "AG17") (pinfunction "GND_AG17") (pintype "power_in"))
      (node (ref "IC19") (pin "AG19") (pinfunction "GND_AG19") (pintype "power_in"))
      (node (ref "IC19") (pin "AH11") (pinfunction "GND_AH11") (pintype "power_in"))
      (node (ref "IC19") (pin "AH21") (pinfunction "GND_AH21") (pintype "power_in"))
      (node (ref "IC19") (pin "AH23") (pinfunction "GND_AH23") (pintype "power_in"))
      (node (ref "IC19") (pin "AH28") (pinfunction "GND_AH28") (pintype "power_in"))
      (node (ref "IC19") (pin "AH9") (pinfunction "GND_AH9") (pintype "power_in"))
      (node (ref "IC19") (pin "AJ10") (pinfunction "GND_AJ10") (pintype "power_in"))
      (node (ref "IC19") (pin "AJ12") (pinfunction "GND_AJ12") (pintype "power_in"))
      (node (ref "IC19") (pin "AJ20") (pinfunction "GND_AJ20") (pintype "power_in"))
      (node (ref "IC19") (pin "AJ22") (pinfunction "GND_AJ22") (pintype "power_in"))
      (node (ref "IC19") (pin "AJ24") (pinfunction "GND_AJ24") (pintype "power_in"))
      (node (ref "IC19") (pin "AJ5") (pinfunction "GND_AJ5") (pintype "power_in"))
      (node (ref "IC19") (pin "AJ8") (pinfunction "GND_AJ8") (pintype "power_in"))
      (node (ref "IC19") (pin "AK1") (pinfunction "GND_AK1") (pintype "power_in"))
      (node (ref "IC19") (pin "AK12") (pinfunction "GND_AK12") (pintype "power_in"))
      (node (ref "IC19") (pin "AK14") (pinfunction "GND_AK14") (pintype "power_in"))
      (node (ref "IC19") (pin "AK18") (pinfunction "GND_AK18") (pintype "power_in"))
      (node (ref "IC19") (pin "AK20") (pinfunction "GND_AK20") (pintype "power_in"))
      (node (ref "IC19") (pin "AK24") (pinfunction "GND_AK24") (pintype "power_in"))
      (node (ref "IC19") (pin "AK30") (pinfunction "GND_AK30") (pintype "power_in"))
      (node (ref "IC19") (pin "AK8") (pinfunction "GND_AK8") (pintype "power_in"))
      (node (ref "IC19") (pin "B10") (pinfunction "GND_B10") (pintype "power_in"))
      (node (ref "IC19") (pin "B12") (pinfunction "GND_B12") (pintype "power_in"))
      (node (ref "IC19") (pin "B20") (pinfunction "GND_B20") (pintype "power_in"))
      (node (ref "IC19") (pin "B22") (pinfunction "GND_B22") (pintype "power_in"))
      (node (ref "IC19") (pin "B24") (pinfunction "GND_B24") (pintype "power_in"))
      (node (ref "IC19") (pin "B26") (pinfunction "GND_B26") (pintype "power_in"))
      (node (ref "IC19") (pin "B8") (pinfunction "GND_B8") (pintype "power_in"))
      (node (ref "IC19") (pin "C11") (pinfunction "GND_C11") (pintype "power_in"))
      (node (ref "IC19") (pin "C21") (pinfunction "GND_C21") (pintype "power_in"))
      (node (ref "IC19") (pin "C23") (pinfunction "GND_C23") (pintype "power_in"))
      (node (ref "IC19") (pin "C28") (pinfunction "GND_C28") (pintype "power_in"))
      (node (ref "IC19") (pin "C3") (pinfunction "GND_C3") (pintype "power_in"))
      (node (ref "IC19") (pin "C9") (pinfunction "GND_C9") (pintype "power_in"))
      (node (ref "IC19") (pin "D13") (pinfunction "GND_D13") (pintype "power_in"))
      (node (ref "IC19") (pin "D15") (pinfunction "GND_D15") (pintype "power_in"))
      (node (ref "IC19") (pin "D17") (pinfunction "GND_D17") (pintype "power_in"))
      (node (ref "IC19") (pin "D19") (pinfunction "GND_D19") (pintype "power_in"))
      (node (ref "IC19") (pin "E10") (pinfunction "GND_E10") (pintype "power_in"))
      (node (ref "IC19") (pin "E18") (pinfunction "GND_E18") (pintype "power_in"))
      (node (ref "IC19") (pin "E2") (pinfunction "GND_E2") (pintype "power_in"))
      (node (ref "IC19") (pin "E20") (pinfunction "GND_E20") (pintype "power_in"))
      (node (ref "IC19") (pin "E22") (pinfunction "GND_E22") (pintype "power_in"))
      (node (ref "IC19") (pin "F29") (pinfunction "GND_F29") (pintype "power_in"))
      (node (ref "IC19") (pin "F5") (pinfunction "GND_F5") (pintype "power_in"))
      (node (ref "IC19") (pin "F7") (pinfunction "GND_F7") (pintype "power_in"))
      (node (ref "IC19") (pin "G24") (pinfunction "GND_G24") (pintype "power_in"))
      (node (ref "IC19") (pin "J11") (pinfunction "GND_J11") (pintype "power_in"))
      (node (ref "IC19") (pin "J16") (pinfunction "GND_J16") (pintype "power_in"))
      (node (ref "IC19") (pin "J2") (pinfunction "GND_J2") (pintype "power_in"))
      (node (ref "IC19") (pin "J21") (pinfunction "GND_J21") (pintype "power_in"))
      (node (ref "IC19") (pin "J26") (pinfunction "GND_J26") (pintype "power_in"))
      (node (ref "IC19") (pin "K16") (pinfunction "GND_K16") (pintype "power_in"))
      (node (ref "IC19") (pin "K18") (pinfunction "GND_K18") (pintype "power_in"))
      (node (ref "IC19") (pin "K22") (pinfunction "GND_K22") (pintype "power_in"))
      (node (ref "IC19") (pin "K23") (pinfunction "GND_K23") (pintype "power_in"))
      (node (ref "IC19") (pin "K29") (pinfunction "GND_K29") (pintype "power_in"))
      (node (ref "IC19") (pin "K5") (pinfunction "GND_K5") (pintype "power_in"))
      (node (ref "IC19") (pin "K7") (pinfunction "GND_K7") (pintype "power_in"))
      (node (ref "IC19") (pin "K8") (pinfunction "GND_K8") (pintype "power_in"))
      (node (ref "IC19") (pin "K9") (pinfunction "GND_K9") (pintype "power_in"))
      (node (ref "IC19") (pin "L16") (pinfunction "GND_L16") (pintype "power_in"))
      (node (ref "IC19") (pin "L23") (pinfunction "GND_L23") (pintype "power_in"))
      (node (ref "IC19") (pin "L8") (pinfunction "GND_L8") (pintype "power_in"))
      (node (ref "IC19") (pin "M12") (pinfunction "GND_M12") (pintype "power_in"))
      (node (ref "IC19") (pin "M16") (pinfunction "GND_M16") (pintype "power_in"))
      (node (ref "IC19") (pin "M22") (pinfunction "GND_M22") (pintype "power_in"))
      (node (ref "IC19") (pin "M9") (pinfunction "GND_M9") (pintype "power_in"))
      (node (ref "IC19") (pin "N13") (pinfunction "GND_N13") (pintype "power_in"))
      (node (ref "IC19") (pin "N14") (pinfunction "GND_N14") (pintype "power_in"))
      (node (ref "IC19") (pin "N17") (pinfunction "GND_N17") (pintype "power_in"))
      (node (ref "IC19") (pin "N18") (pinfunction "GND_N18") (pintype "power_in"))
      (node (ref "IC19") (pin "N2") (pinfunction "GND_N2") (pintype "power_in"))
      (node (ref "IC19") (pin "N21") (pinfunction "GND_N21") (pintype "power_in"))
      (node (ref "IC19") (pin "N22") (pinfunction "GND_N22") (pintype "power_in"))
      (node (ref "IC19") (pin "N26") (pinfunction "GND_N26") (pintype "power_in"))
      (node (ref "IC19") (pin "P10") (pinfunction "GND_P10") (pintype "power_in"))
      (node (ref "IC19") (pin "P13") (pinfunction "GND_P13") (pintype "power_in"))
      (node (ref "IC19") (pin "P14") (pinfunction "GND_P14") (pintype "power_in"))
      (node (ref "IC19") (pin "P17") (pinfunction "GND_P17") (pintype "power_in"))
      (node (ref "IC19") (pin "P18") (pinfunction "GND_P18") (pintype "power_in"))
      (node (ref "IC19") (pin "P20") (pinfunction "GND_P20") (pintype "power_in"))
      (node (ref "IC19") (pin "P29") (pinfunction "GND_P29") (pintype "power_in"))
      (node (ref "IC19") (pin "P5") (pinfunction "GND_P5") (pintype "power_in"))
      (node (ref "IC19") (pin "P8") (pinfunction "GND_P8") (pintype "power_in"))
      (node (ref "IC19") (pin "R11") (pinfunction "GND_R11") (pintype "power_in"))
      (node (ref "IC19") (pin "R12") (pinfunction "GND_R12") (pintype "power_in"))
      (node (ref "IC19") (pin "R15") (pinfunction "GND_R15") (pintype "power_in"))
      (node (ref "IC19") (pin "R16") (pinfunction "GND_R16") (pintype "power_in"))
      (node (ref "IC19") (pin "R19") (pinfunction "GND_R19") (pintype "power_in"))
      (node (ref "IC19") (pin "R20") (pinfunction "GND_R20") (pintype "power_in"))
      (node (ref "IC19") (pin "R9") (pinfunction "GND_R9") (pintype "power_in"))
      (node (ref "IC19") (pin "T10") (pinfunction "GND_T10") (pintype "power_in"))
      (node (ref "IC19") (pin "T11") (pinfunction "GND_T11") (pintype "power_in"))
      (node (ref "IC19") (pin "T12") (pinfunction "GND_T12") (pintype "power_in"))
      (node (ref "IC19") (pin "T15") (pinfunction "GND_T15") (pintype "power_in"))
      (node (ref "IC19") (pin "T16") (pinfunction "GND_T16") (pintype "power_in"))
      (node (ref "IC19") (pin "T19") (pinfunction "GND_T19") (pintype "power_in"))
      (node (ref "IC19") (pin "T20") (pinfunction "GND_T20") (pintype "power_in"))
      (node (ref "IC19") (pin "T22") (pinfunction "GND_T22") (pintype "power_in"))
      (node (ref "IC19") (pin "T23") (pinfunction "GND_T23") (pintype "power_in"))
      (node (ref "IC19") (pin "U13") (pinfunction "GND_U13") (pintype "power_in"))
      (node (ref "IC19") (pin "U14") (pinfunction "GND_U14") (pintype "power_in"))
      (node (ref "IC19") (pin "U17") (pinfunction "GND_U17") (pintype "power_in"))
      (node (ref "IC19") (pin "U18") (pinfunction "GND_U18") (pintype "power_in"))
      (node (ref "IC19") (pin "U2") (pinfunction "GND_U2") (pintype "power_in"))
      (node (ref "IC19") (pin "U21") (pinfunction "GND_U21") (pintype "power_in"))
      (node (ref "IC19") (pin "U22") (pinfunction "GND_U22") (pintype "power_in"))
      (node (ref "IC19") (pin "U26") (pinfunction "GND_U26") (pintype "power_in"))
      (node (ref "IC19") (pin "U9") (pinfunction "GND_U9") (pintype "power_in"))
      (node (ref "IC19") (pin "V13") (pinfunction "GND_V13") (pintype "power_in"))
      (node (ref "IC19") (pin "V14") (pinfunction "GND_V14") (pintype "power_in"))
      (node (ref "IC19") (pin "V17") (pinfunction "GND_V17") (pintype "power_in"))
      (node (ref "IC19") (pin "V18") (pinfunction "GND_V18") (pintype "power_in"))
      (node (ref "IC19") (pin "V22") (pinfunction "GND_V22") (pintype "power_in"))
      (node (ref "IC19") (pin "V29") (pinfunction "GND_V29") (pintype "power_in"))
      (node (ref "IC19") (pin "V5") (pinfunction "GND_V5") (pintype "power_in"))
      (node (ref "IC19") (pin "W16") (pinfunction "GND_W16") (pintype "power_in"))
      (node (ref "IC19") (pin "W18") (pinfunction "GND_W18") (pintype "power_in"))
      (node (ref "IC19") (pin "W8") (pinfunction "GND_W8") (pintype "power_in"))
      (node (ref "R13") (pin "1") (pinfunction "1_1") (pintype "passive"))
    )
    (net (code "2") (name "Net-(BATH1-PLUS)") (class "Default")
      (node (ref "BATH1") (pin "1") (pinfunction "PLUS_1") (pintype "input"))
      (node (ref "C32") (pin "2") (pinfunction "2_2") (pintype "passive"))
      (node (ref "IC19") (pin "AB26") (pinfunction "VBATT_AB26") (pintype "input"))
    )
    (net (code "3") (name "Net-(IC19O-RFUSE)") (class "Default")
      (node (ref "IC19") (pin "AB27") (pinfunction "RFUSE_AB27") (pintype "input"))
      (node (ref "R239") (pin "2") (pinfunction "2_2") (pintype "passive"))
    )
    (net (code "4") (name "Net-(IC19O-VFS)") (class "Default")
      (node (ref "C30") (pin "2") (pinfunction "2_2") (pintype "passive"))
      (node (ref "IC19") (pin "AF27") (pinfunction "VFS_AF27") (pintype "input"))
      (node (ref "R97") (pin "2") (pinfunction "2_2") (pintype "passive"))
    )
    (net (code "5") (name "Net-(R13-Pad2)") (class "Default")
      (node (ref "R13") (pin "2") (pinfunction "2_2") (pintype "passive"))
      (node (ref "R239") (pin "1") (pinfunction "1_1") (pintype "passive"))
    )
    (net (code "6") (name "P1V2") (class "Default")
      (node (ref "C134") (pin "2") (pinfunction "2_2") (pintype "passive"))
      (node (ref "C140") (pin "2") (pinfunction "2_2") (pintype "passive"))
      (node (ref "C146") (pin "2") (pinfunction "2_2") (pintype "passive"))
      (node (ref "C147") (pin "2") (pinfunction "2_2") (pintype "passive"))
      (node (ref "C159") (pin "2") (pinfunction "2_2") (pintype "passive"))
      (node (ref "C160") (pin "2") (pinfunction "2_2") (pintype "passive"))
      (node (ref "C174") (pin "2") (pinfunction "2_2") (pintype "passive"))
      (node (ref "C177") (pin "2") (pinfunction "2_2") (pintype "passive"))
      (node (ref "C192") (pin "2") (pinfunction "2_2") (pintype "passive"))
      (node (ref "C193") (pin "2") (pinfunction "2_2") (pintype "passive"))
      (node (ref "C201") (pin "2") (pinfunction "2_2") (pintype "passive"))
      (node (ref "C203") (pin "2") (pinfunction "2_2") (pintype "passive"))
      (node (ref "C223") (pin "2") (pinfunction "2_2") (pintype "passive"))
      (node (ref "C229") (pin "2") (pinfunction "2_2") (pintype "passive"))
      (node (ref "C24") (pin "2") (pinfunction "2_2") (pintype "passive"))
      (node (ref "C25") (pin "2") (pinfunction "2_2") (pintype "passive"))
      (node (ref "C381") (pin "2") (pinfunction "2_2") (pintype "passive"))
      (node (ref "C382") (pin "2") (pinfunction "2_2") (pintype "passive"))
      (node (ref "IC19") (pin "N11") (pinfunction "VCCINT_N11") (pintype "power_in"))
      (node (ref "IC19") (pin "N12") (pinfunction "VCCINT_N12") (pintype "power_in"))
      (node (ref "IC19") (pin "N15") (pinfunction "VCCINT_N15") (pintype "power_in"))
      (node (ref "IC19") (pin "N16") (pinfunction "VCCINT_N16") (pintype "power_in"))
      (node (ref "IC19") (pin "N19") (pinfunction "VCCINT_N19") (pintype "power_in"))
      (node (ref "IC19") (pin "N20") (pinfunction "VCCINT_N20") (pintype "power_in"))
      (node (ref "IC19") (pin "P11") (pinfunction "VCCINT_P11") (pintype "power_in"))
      (node (ref "IC19") (pin "P12") (pinfunction "VCCINT_P12") (pintype "power_in"))
      (node (ref "IC19") (pin "P15") (pinfunction "VCCINT_P15") (pintype "power_in"))
      (node (ref "IC19") (pin "P16") (pinfunction "VCCINT_P16") (pintype "power_in"))
      (node (ref "IC19") (pin "P19") (pinfunction "VCCINT_P19") (pintype "power_in"))
      (node (ref "IC19") (pin "R13") (pinfunction "VCCINT_R13") (pintype "power_in"))
      (node (ref "IC19") (pin "R14") (pinfunction "VCCINT_R14") (pintype "power_in"))
      (node (ref "IC19") (pin "R17") (pinfunction "VCCINT_R17") (pintype "power_in"))
      (node (ref "IC19") (pin "R18") (pinfunction "VCCINT_R18") (pintype "power_in"))
      (node (ref "IC19") (pin "T13") (pinfunction "VCCINT_T13") (pintype "power_in"))
      (node (ref "IC19") (pin "T14") (pinfunction "VCCINT_T14") (pintype "power_in"))
      (node (ref "IC19") (pin "T17") (pinfunction "VCCINT_T17") (pintype "power_in"))
      (node (ref "IC19") (pin "T18") (pinfunction "VCCINT_T18") (pintype "power_in"))
      (node (ref "IC19") (pin "U11") (pinfunction "VCCINT_U11") (pintype "power_in"))
      (node (ref "IC19") (pin "U12") (pinfunction "VCCINT_U12") (pintype "power_in"))
      (node (ref "IC19") (pin "U15") (pinfunction "VCCINT_U15") (pintype "power_in"))
      (node (ref "IC19") (pin "U16") (pinfunction "VCCINT_U16") (pintype "power_in"))
      (node (ref "IC19") (pin "U19") (pinfunction "VCCINT_U19") (pintype "power_in"))
      (node (ref "IC19") (pin "U20") (pinfunction "VCCINT_U20") (pintype "power_in"))
      (node (ref "IC19") (pin "V11") (pinfunction "VCCINT_V11") (pintype "power_in"))
      (node (ref "IC19") (pin "V12") (pinfunction "VCCINT_V12") (pintype "power_in"))
      (node (ref "IC19") (pin "V15") (pinfunction "VCCINT_V15") (pintype "power_in"))
      (node (ref "IC19") (pin "V16") (pinfunction "VCCINT_V16") (pintype "power_in"))
      (node (ref "IC19") (pin "V19") (pinfunction "VCCINT_V19") (pintype "power_in"))
      (node (ref "IC19") (pin "V20") (pinfunction "VCCINT_V20") (pintype "power_in"))
    )
    (net (code "7") (name "P1V5") (class "Default")
      (node (ref "C121") (pin "2") (pinfunction "2_2") (pintype "passive"))
      (node (ref "C141") (pin "2") (pinfunction "2_2") (pintype "passive"))
      (node (ref "C149") (pin "2") (pinfunction "2_2") (pintype "passive"))
      (node (ref "C161") (pin "2") (pinfunction "2_2") (pintype "passive"))
      (node (ref "C178") (pin "2") (pinfunction "2_2") (pintype "passive"))
      (node (ref "C194") (pin "2") (pinfunction "2_2") (pintype "passive"))
      (node (ref "C204") (pin "2") (pinfunction "2_2") (pintype "passive"))
      (node (ref "C230") (pin "2") (pinfunction "2_2") (pintype "passive"))
      (node (ref "C28") (pin "2") (pinfunction "2_2") (pintype "passive"))
      (node (ref "IC19") (pin "B28") (pinfunction "VCCO_5_B28") (pintype "power_in"))
      (node (ref "IC19") (pin "B4") (pinfunction "VCCO_4_B4") (pintype "power_in"))
      (node (ref "IC19") (pin "C2") (pinfunction "VCCO_4_C2") (pintype "power_in"))
      (node (ref "IC19") (pin "D29") (pinfunction "VCCO_5_D29") (pintype "power_in"))
      (node (ref "IC19") (pin "G2") (pinfunction "VCCO_4_G2") (pintype "power_in"))
      (node (ref "IC19") (pin "G26") (pinfunction "VCCO_5_G26") (pintype "power_in"))
      (node (ref "IC19") (pin "H29") (pinfunction "VCCO_5_H29") (pintype "power_in"))
      (node (ref "IC19") (pin "H5") (pinfunction "VCCO_4_H5") (pintype "power_in"))
      (node (ref "IC19") (pin "J25") (pinfunction "VCCO_5_J25") (pintype "power_in"))
      (node (ref "IC19") (pin "K24") (pinfunction "VCCO_5_K24") (pintype "power_in"))
      (node (ref "IC19") (pin "K6") (pinfunction "VCCO_4_K6") (pintype "power_in"))
      (node (ref "IC19") (pin "L2") (pinfunction "VCCO_4_L2") (pintype "power_in"))
      (node (ref "IC19") (pin "L26") (pinfunction "VCCO_5_L26") (pintype "power_in"))
      (node (ref "IC19") (pin "M29") (pinfunction "VCCO_5_M29") (pintype "power_in"))
      (node (ref "IC19") (pin "M5") (pinfunction "VCCO_4_M5") (pintype "power_in"))
    )
    (net (code "8") (name "P2V5") (class "Default")
      (node (ref "C1") (pin "2") (pinfunction "2_2") (pintype "passive"))
      (node (ref "C120") (pin "2") (pinfunction "2_2") (pintype "passive"))
      (node (ref "C122") (pin "2") (pinfunction "2_2") (pintype "passive"))
      (node (ref "C123") (pin "2") (pinfunction "2_2") (pintype "passive"))
      (node (ref "C124") (pin "2") (pinfunction "2_2") (pintype "passive"))
      (node (ref "C126") (pin "2") (pinfunction "2_2") (pintype "passive"))
      (node (ref "C129") (pin "2") (pinfunction "2_2") (pintype "passive"))
      (node (ref "C142") (pin "2") (pinfunction "2_2") (pintype "passive"))
      (node (ref "C151") (pin "2") (pinfunction "2_2") (pintype "passive"))
      (node (ref "C168") (pin "2") (pinfunction "2_2") (pintype "passive"))
      (node (ref "C187") (pin "2") (pinfunction "2_2") (pintype "passive"))
      (node (ref "C188") (pin "2") (pinfunction "2_2") (pintype "passive"))
      (node (ref "C196") (pin "2") (pinfunction "2_2") (pintype "passive"))
      (node (ref "C205") (pin "2") (pinfunction "2_2") (pintype "passive"))
      (node (ref "C215") (pin "2") (pinfunction "2_2") (pintype "passive"))
      (node (ref "C347") (pin "2") (pinfunction "2_2") (pintype "passive"))
      (node (ref "C374") (pin "2") (pinfunction "2_2") (pintype "passive"))
      (node (ref "C375") (pin "2") (pinfunction "2_2") (pintype "passive"))
      (node (ref "IC19") (pin "AA12") (pinfunction "VCCO_2_AA12") (pintype "power_in"))
      (node (ref "IC19") (pin "AA16") (pinfunction "VCCO_2_AA16") (pintype "power_in"))
      (node (ref "IC19") (pin "AA20") (pinfunction "VCCO_2_AA20") (pintype "power_in"))
      (node (ref "IC19") (pin "AC10") (pinfunction "VCCO_2_AC10") (pintype "power_in"))
      (node (ref "IC19") (pin "AC18") (pinfunction "VCCO_2_AC18") (pintype "power_in"))
      (node (ref "IC19") (pin "AD13") (pinfunction "VCCO_2_AD13") (pintype "power_in"))
      (node (ref "IC19") (pin "AD21") (pinfunction "VCCO_2_AD21") (pintype "power_in"))
      (node (ref "IC19") (pin "AD23") (pinfunction "VCCO_2_AD23") (pintype "power_in"))
      (node (ref "IC19") (pin "AE16") (pinfunction "VCCO_2_AE16") (pintype "power_in"))
      (node (ref "IC19") (pin "AF8") (pinfunction "VCCO_2_AF8") (pintype "power_in"))
      (node (ref "IC19") (pin "AH25") (pinfunction "VCCO_2_AH25") (pintype "power_in"))
      (node (ref "IC19") (pin "AJ16") (pinfunction "VCCO_2_AJ16") (pintype "power_in"))
      (node (ref "IC19") (pin "AJ7") (pinfunction "VCCO_2_AJ7") (pintype "power_in"))
      (node (ref "IC19") (pin "B16") (pinfunction "VCCO_0_B16") (pintype "power_in"))
      (node (ref "IC19") (pin "C25") (pinfunction "VCCO_0_C25") (pintype "power_in"))
      (node (ref "IC19") (pin "C7") (pinfunction "VCCO_0_C7") (pintype "power_in"))
      (node (ref "IC19") (pin "F16") (pinfunction "VCCO_0_F16") (pintype "power_in"))
      (node (ref "IC19") (pin "G13") (pinfunction "VCCO_0_G13") (pintype "power_in"))
      (node (ref "IC19") (pin "G23") (pinfunction "VCCO_0_G23") (pintype "power_in"))
      (node (ref "IC19") (pin "G8") (pinfunction "VCCO_0_G8") (pintype "power_in"))
      (node (ref "IC19") (pin "H10") (pinfunction "VCCO_0_H10") (pintype "power_in"))
      (node (ref "IC19") (pin "H20") (pinfunction "VCCO_0_H20") (pintype "power_in"))
      (node (ref "IC19") (pin "J17") (pinfunction "VCCO_0_J17") (pintype "power_in"))
      (node (ref "IC19") (pin "K13") (pinfunction "VCCO_0_K13") (pintype "power_in"))
      (node (ref "IC19") (pin "L15") (pinfunction "VCCO_0_L15") (pintype "power_in"))
      (node (ref "IC19") (pin "L9") (pinfunction "VCCO_0_L9") (pintype "power_in"))
      (node (ref "IC19") (pin "M17") (pinfunction "VCCO_0_M17") (pintype "power_in"))
      (node (ref "IC19") (pin "M21") (pinfunction "VCCO_0_M21") (pintype "power_in"))
    )
    (net (code "9") (name "P3V3") (class "Default")
      (node (ref "C130") (pin "2") (pinfunction "2_2") (pintype "passive"))
      (node (ref "C131") (pin "2") (pinfunction "2_2") (pintype "passive"))
      (node (ref "C133") (pin "2") (pinfunction "2_2") (pintype "passive"))
      (node (ref "C14") (pin "2") (pinfunction "2_2") (pintype "passive"))
      (node (ref "C143") (pin "2") (pinfunction "2_2") (pintype "passive"))
      (node (ref "C144") (pin "2") (pinfunction "2_2") (pintype "passive"))
      (node (ref "C145") (pin "2") (pinfunction "2_2") (pintype "passive"))
      (node (ref "C155") (pin "2") (pinfunction "2_2") (pintype "passive"))
      (node (ref "C156") (pin "2") (pinfunction "2_2") (pintype "passive"))
      (node (ref "C158") (pin "2") (pinfunction "2_2") (pintype "passive"))
      (node (ref "C170") (pin "2") (pinfunction "2_2") (pintype "passive"))
      (node (ref "C171") (pin "2") (pinfunction "2_2") (pintype "passive"))
      (node (ref "C172") (pin "2") (pinfunction "2_2") (pintype "passive"))
      (node (ref "C189") (pin "2") (pinfunction "2_2") (pintype "passive"))
      (node (ref "C190") (pin "2") (pinfunction "2_2") (pintype "passive"))
      (node (ref "C191") (pin "2") (pinfunction "2_2") (pintype "passive"))
      (node (ref "C197") (pin "2") (pinfunction "2_2") (pintype "passive"))
      (node (ref "C198") (pin "2") (pinfunction "2_2") (pintype "passive"))
      (node (ref "C199") (pin "2") (pinfunction "2_2") (pintype "passive"))
      (node (ref "C217") (pin "2") (pinfunction "2_2") (pintype "passive"))
      (node (ref "C221") (pin "2") (pinfunction "2_2") (pintype "passive"))
      (node (ref "C222") (pin "2") (pinfunction "2_2") (pintype "passive"))
      (node (ref "C377") (pin "2") (pinfunction "2_2") (pintype "passive"))
      (node (ref "C379") (pin "2") (pinfunction "2_2") (pintype "passive"))
      (node (ref "C380") (pin "2") (pinfunction "2_2") (pintype "passive"))
      (node (ref "C8") (pin "2") (pinfunction "2_2") (pintype "passive"))
      (node (ref "C9") (pin "2") (pinfunction "2_2") (pintype "passive"))
      (node (ref "IC19") (pin "AA23") (pinfunction "VCCO_1_AA23") (pintype "power_in"))
      (node (ref "IC19") (pin "AA8") (pinfunction "VCCO_3_AA8") (pintype "power_in"))
      (node (ref "IC19") (pin "AB24") (pinfunction "VCCAUX_AB24") (pintype "power_in"))
      (node (ref "IC19") (pin "AC2") (pinfunction "VCCO_3_AC2") (pintype "power_in"))
      (node (ref "IC19") (pin "AC26") (pinfunction "VCCO_1_AC26") (pintype "power_in"))
      (node (ref "IC19") (pin "AC7") (pinfunction "VCCAUX_AC7") (pintype "power_in"))
      (node (ref "IC19") (pin "AD29") (pinfunction "VCCO_1_AD29") (pintype "power_in"))
      (node (ref "IC19") (pin "AD5") (pinfunction "VCCO_3_AD5") (pintype "power_in"))
      (node (ref "IC19") (pin "AG2") (pinfunction "VCCO_3_AG2") (pintype "power_in"))
      (node (ref "IC19") (pin "AG23") (pinfunction "VCCAUX_AG23") (pintype "power_in"))
      (node (ref "IC19") (pin "AG9") (pinfunction "VCCAUX_AG9") (pintype "power_in"))
      (node (ref "IC19") (pin "AH29") (pinfunction "VCCO_1_AH29") (pintype "power_in"))
      (node (ref "IC19") (pin "AJ27") (pinfunction "VCCO_1_AJ27") (pintype "power_in"))
      (node (ref "IC19") (pin "AJ3") (pinfunction "VCCO_3_AJ3") (pintype "power_in"))
      (node (ref "IC19") (pin "D23") (pinfunction "VCCAUX_D23") (pintype "power_in"))
      (node (ref "IC19") (pin "D9") (pinfunction "VCCAUX_D9") (pintype "power_in"))
      (node (ref "IC19") (pin "G6") (pinfunction "VCCAUX_G6") (pintype "power_in"))
      (node (ref "IC19") (pin "H24") (pinfunction "VCCAUX_H24") (pintype "power_in"))
      (node (ref "IC19") (pin "J15") (pinfunction "VCCAUX_J15") (pintype "power_in"))
      (node (ref "IC19") (pin "J23") (pinfunction "VCCAUX_J23") (pintype "power_in"))
      (node (ref "IC19") (pin "J7") (pinfunction "VCCAUX_J7") (pintype "power_in"))
      (node (ref "IC19") (pin "J9") (pinfunction "VCCAUX_J9") (pintype "power_in"))
      (node (ref "IC19") (pin "L22") (pinfunction "VCCAUX_L22") (pintype "power_in"))
      (node (ref "IC19") (pin "M11") (pinfunction "VCCAUX_M11") (pintype "power_in"))
      (node (ref "IC19") (pin "M14") (pinfunction "VCCAUX_M14") (pintype "power_in"))
      (node (ref "IC19") (pin "M25") (pinfunction "VCCAUX_M25") (pintype "power_in"))
      (node (ref "IC19") (pin "M8") (pinfunction "VCCO_3_M8") (pintype "power_in"))
      (node (ref "IC19") (pin "N23") (pinfunction "VCCO_1_N23") (pintype "power_in"))
      (node (ref "IC19") (pin "N6") (pinfunction "VCCAUX_N6") (pintype "power_in"))
      (node (ref "IC19") (pin "P21") (pinfunction "VCCO_1_P21") (pintype "power_in"))
      (node (ref "IC19") (pin "P9") (pinfunction "VCCO_3_P9") (pintype "power_in"))
      (node (ref "IC19") (pin "R10") (pinfunction "VCCAUX_R10") (pintype "power_in"))
      (node (ref "IC19") (pin "R2") (pinfunction "VCCO_3_R2") (pintype "power_in"))
      (node (ref "IC19") (pin "R23") (pinfunction "VCCO_1_R23") (pintype "power_in"))
      (node (ref "IC19") (pin "R26") (pinfunction "VCCO_1_R26") (pintype "power_in"))
      (node (ref "IC19") (pin "R8") (pinfunction "VCCO_3_R8") (pintype "power_in"))
      (node (ref "IC19") (pin "T21") (pinfunction "VCCAUX_T21") (pintype "power_in"))
      (node (ref "IC19") (pin "T29") (pinfunction "VCCO_1_T29") (pintype "power_in"))
      (node (ref "IC19") (pin "T5") (pinfunction "VCCO_3_T5") (pintype "power_in"))
      (node (ref "IC19") (pin "U10") (pinfunction "VCCAUX_U10") (pintype "power_in"))
      (node (ref "IC19") (pin "U23") (pinfunction "VCCO_1_U23") (pintype "power_in"))
      (node (ref "IC19") (pin "U8") (pinfunction "VCCO_3_U8") (pintype "power_in"))
      (node (ref "IC19") (pin "V21") (pinfunction "VCCAUX_V21") (pintype "power_in"))
      (node (ref "IC19") (pin "V25") (pinfunction "VCCAUX_V25") (pintype "power_in"))
      (node (ref "IC19") (pin "V6") (pinfunction "VCCAUX_V6") (pintype "power_in"))
      (node (ref "IC19") (pin "W13") (pinfunction "VCCAUX_W13") (pintype "power_in"))
      (node (ref "IC19") (pin "W15") (pinfunction "VCCAUX_W15") (pintype "power_in"))
      (node (ref "IC19") (pin "W17") (pinfunction "VCCAUX_W17") (pintype "power_in"))
      (node (ref "IC19") (pin "W2") (pinfunction "VCCO_3_W2") (pintype "power_in"))
      (node (ref "IC19") (pin "W23") (pinfunction "VCCO_1_W23") (pintype "power_in"))
      (node (ref "IC19") (pin "W26") (pinfunction "VCCO_1_W26") (pintype "power_in"))
      (node (ref "IC19") (pin "Y10") (pinfunction "VCCO_3_Y10") (pintype "power_in"))
      (node (ref "IC19") (pin "Y18") (pinfunction "VCCAUX_Y18") (pintype "power_in"))
      (node (ref "IC19") (pin "Y29") (pinfunction "VCCO_1_Y29") (pintype "power_in"))
      (node (ref "IC19") (pin "Y5") (pinfunction "VCCO_3_Y5") (pintype "power_in"))
      (node (ref "R97") (pin "1") (pinfunction "1_1") (pintype "passive"))
    )
  )
)
